# CortexM0_development_board.net
KiCad netlist of a schematic drawn in EAGLE
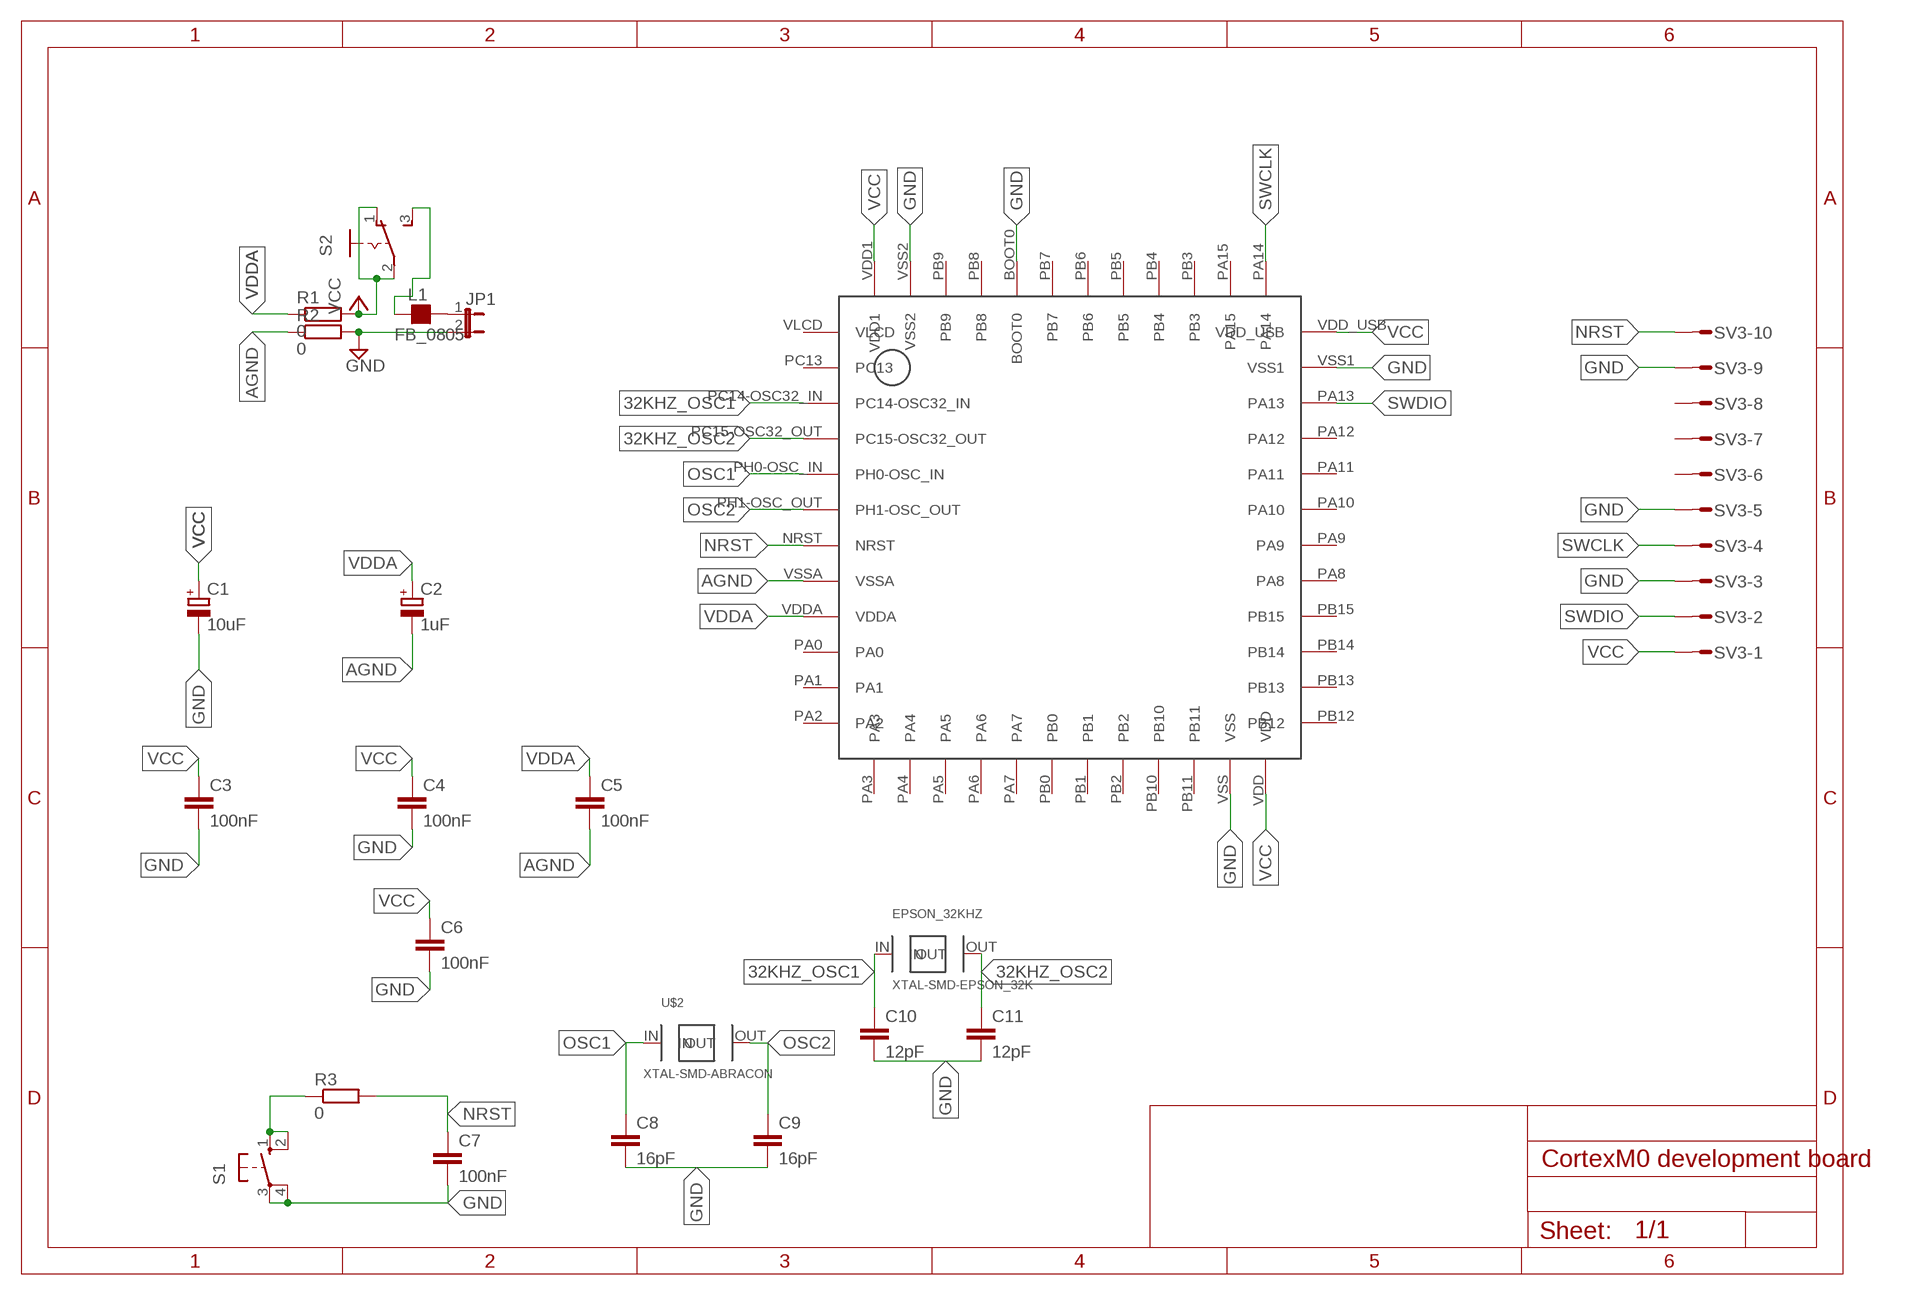
[diagram p0: schematic, sheet 1]

(export (version "E")
  (design (tool "Eeschema 10.0.6"))
  (components
    (comp (ref "C1")
      (value "10uF")
      (footprint "eagle-import:PANASONIC_B")
      (libsource (lib "eagle-import") (part "CPOL-EUB"))
    )
    (comp (ref "C2")
      (value "1uF")
      (footprint "eagle-import:PANASONIC_B")
      (libsource (lib "eagle-import") (part "CPOL-EUB"))
    )
    (comp (ref "C3")
      (value "100nF")
      (footprint "eagle-import:C0805")
      (libsource (lib "eagle-import") (part "C-EUC0805"))
    )
    (comp (ref "C4")
      (value "100nF")
      (footprint "eagle-import:C0805")
      (libsource (lib "eagle-import") (part "C-EUC0805"))
    )
    (comp (ref "C5")
      (value "100nF")
      (footprint "eagle-import:C0805")
      (libsource (lib "eagle-import") (part "C-EUC0805"))
    )
    (comp (ref "C6")
      (value "100nF")
      (footprint "eagle-import:C0805")
      (libsource (lib "eagle-import") (part "C-EUC0805"))
    )
    (comp (ref "C7")
      (value "100nF")
      (footprint "eagle-import:C0805")
      (libsource (lib "eagle-import") (part "C-EUC0805"))
    )
    (comp (ref "C8")
      (value "16pF")
      (footprint "eagle-import:C0805")
      (libsource (lib "eagle-import") (part "C-EUC0805"))
    )
    (comp (ref "C9")
      (value "16pF")
      (footprint "eagle-import:C0805")
      (libsource (lib "eagle-import") (part "C-EUC0805"))
    )
    (comp (ref "C10")
      (value "12pF")
      (footprint "eagle-import:C0805")
      (libsource (lib "eagle-import") (part "C-EUC0805"))
    )
    (comp (ref "C11")
      (value "12pF")
      (footprint "eagle-import:C0805")
      (libsource (lib "eagle-import") (part "C-EUC0805"))
    )
    (comp (ref "EPSON_32KHZ")
      (value "XTAL-SMD-EPSON_32K")
      (footprint "eagle-import:XTAL-EPSON-FC135R")
      (libsource (lib "eagle-import") (part "XTAL-SMD-EPSON_32K"))
    )
    (comp (ref "JP1")
      (value "JP1E")
      (footprint "eagle-import:JP1")
      (libsource (lib "eagle-import") (part "JP1E"))
    )
    (comp (ref "L1")
      (value "FB_0805")
      (footprint "eagle-import:L0805")
      (libsource (lib "eagle-import") (part "FB_0805"))
    )
    (comp (ref "R1")
      (value "0")
      (footprint "eagle-import:R0805")
      (libsource (lib "eagle-import") (part "R-EU_R0805"))
    )
    (comp (ref "R2")
      (value "0")
      (footprint "eagle-import:R0805")
      (libsource (lib "eagle-import") (part "R-EU_R0805"))
    )
    (comp (ref "R3")
      (value "0")
      (footprint "eagle-import:R0805")
      (libsource (lib "eagle-import") (part "R-EU_R0805"))
    )
    (comp (ref "S1")
      (value "10-XX")
      (footprint "eagle-import:B3F-10XX")
      (fields (field (name "MPN") "B3F-1000"))
      (libsource (lib "eagle-import") (part "10-XX"))
    )
    (comp (ref "S2")
      (value "255SB")
      (footprint "eagle-import:255SB")
      (libsource (lib "eagle-import") (part "255SB"))
    )
    (comp (ref "SV3")
      (value "S10P")
      (footprint "eagle-import:S10P")
      (libsource (lib "eagle-import") (part "S10P"))
    )
    (comp (ref "U$1")
      (value "STM32L083-LQFP48")
      (footprint "eagle-import:LQFP_48")
      (libsource (lib "eagle-import") (part "STM32L083-LQFP48"))
    )
    (comp (ref "U$2")
      (value "XTAL-SMD-ABRACON")
      (footprint "eagle-import:XTAL-SMD-ABRACON")
      (libsource (lib "eagle-import") (part "XTAL-SMD-ABRACON"))
    )
  )
  (nets
    (net (code "1") (name "32KHZ_OSC1") (class "Default")
      (node (ref "C10") (pin "1") (pinfunction "1_1") (pintype "passive"))
      (node (ref "EPSON_32KHZ") (pin "IN") (pinfunction "IN_IN") (pintype "bidirectional"))
      (node (ref "U$1") (pin "PC14-OSC32_IN") (pinfunction "PC14-OSC32_IN_PC14-OSC32_IN") (pintype "bidirectional"))
    )
    (net (code "2") (name "32KHZ_OSC2") (class "Default")
      (node (ref "C11") (pin "1") (pinfunction "1_1") (pintype "passive"))
      (node (ref "EPSON_32KHZ") (pin "OUT") (pinfunction "OUT_OUT") (pintype "bidirectional"))
      (node (ref "U$1") (pin "PC15-OSC32_OUT") (pinfunction "PC15-OSC32_OUT_PC15-OSC32_OUT") (pintype "bidirectional"))
    )
    (net (code "3") (name "AGND") (class "Default")
      (node (ref "C2") (pin "-") (pinfunction "-_-") (pintype "passive"))
      (node (ref "C5") (pin "2") (pinfunction "2_2") (pintype "passive"))
      (node (ref "R2") (pin "1") (pinfunction "1_1") (pintype "passive"))
      (node (ref "U$1") (pin "VSSA") (pinfunction "VSSA_VSSA") (pintype "bidirectional"))
    )
    (net (code "4") (name "GND") (class "Default")
      (node (ref "C1") (pin "-") (pinfunction "-_-") (pintype "passive"))
      (node (ref "C10") (pin "2") (pinfunction "2_2") (pintype "passive"))
      (node (ref "C11") (pin "2") (pinfunction "2_2") (pintype "passive"))
      (node (ref "C3") (pin "2") (pinfunction "2_2") (pintype "passive"))
      (node (ref "C4") (pin "2") (pinfunction "2_2") (pintype "passive"))
      (node (ref "C6") (pin "2") (pinfunction "2_2") (pintype "passive"))
      (node (ref "C7") (pin "2") (pinfunction "2_2") (pintype "passive"))
      (node (ref "C8") (pin "2") (pinfunction "2_2") (pintype "passive"))
      (node (ref "C9") (pin "2") (pinfunction "2_2") (pintype "passive"))
      (node (ref "JP1") (pin "2") (pinfunction "2_2") (pintype "passive"))
      (node (ref "R2") (pin "2") (pinfunction "2_2") (pintype "passive"))
      (node (ref "S1") (pin "3") (pinfunction "P_3") (pintype "passive"))
      (node (ref "S1") (pin "4") (pinfunction "P1_4") (pintype "passive"))
      (node (ref "SV3") (pin "3") (pinfunction "S_3") (pintype "passive"))
      (node (ref "SV3") (pin "5") (pinfunction "S_5") (pintype "passive"))
      (node (ref "SV3") (pin "9") (pinfunction "S_9") (pintype "passive"))
      (node (ref "U$1") (pin "BOOT0") (pinfunction "BOOT0_BOOT0") (pintype "bidirectional"))
      (node (ref "U$1") (pin "VSS") (pinfunction "VSS_VSS") (pintype "bidirectional"))
      (node (ref "U$1") (pin "VSS1") (pinfunction "VSS1_VSS1") (pintype "bidirectional"))
      (node (ref "U$1") (pin "VSS2") (pinfunction "VSS2_VSS2") (pintype "bidirectional"))
    )
    (net (code "5") (name "NRST") (class "Default")
      (node (ref "C7") (pin "1") (pinfunction "1_1") (pintype "passive"))
      (node (ref "R3") (pin "2") (pinfunction "2_2") (pintype "passive"))
      (node (ref "SV3") (pin "10") (pinfunction "S_10") (pintype "passive"))
      (node (ref "U$1") (pin "NRST") (pinfunction "NRST_NRST") (pintype "bidirectional"))
    )
    (net (code "6") (name "Net-(JP1-Pad1)") (class "Default")
      (node (ref "JP1") (pin "1") (pinfunction "1_1") (pintype "passive"))
      (node (ref "L1") (pin "2") (pinfunction "2_2") (pintype "passive"))
    )
    (net (code "7") (name "Net-(S1-S)") (class "Default")
      (node (ref "R3") (pin "1") (pinfunction "1_1") (pintype "passive"))
      (node (ref "S1") (pin "1") (pinfunction "S_1") (pintype "passive"))
      (node (ref "S1") (pin "2") (pinfunction "S1_2") (pintype "passive"))
    )
    (net (code "8") (name "Net-(S2-S)") (class "Default")
      (node (ref "L1") (pin "1") (pinfunction "1_1") (pintype "passive"))
      (node (ref "S2") (pin "3") (pinfunction "S_3") (pintype "passive"))
    )
    (net (code "9") (name "OSC1") (class "Default")
      (node (ref "C8") (pin "1") (pinfunction "1_1") (pintype "passive"))
      (node (ref "U$1") (pin "PH0-OSC_IN") (pinfunction "PH0-OSC_IN_PH0-OSC_IN") (pintype "bidirectional"))
      (node (ref "U$2") (pin "IN") (pinfunction "IN_IN") (pintype "bidirectional"))
    )
    (net (code "10") (name "OSC2") (class "Default")
      (node (ref "C9") (pin "1") (pinfunction "1_1") (pintype "passive"))
      (node (ref "U$1") (pin "PH1-OSC_OUT") (pinfunction "PH1-OSC_OUT_PH1-OSC_OUT") (pintype "bidirectional"))
      (node (ref "U$2") (pin "OUT") (pinfunction "OUT_OUT") (pintype "bidirectional"))
    )
    (net (code "11") (name "SWCLK") (class "Default")
      (node (ref "SV3") (pin "4") (pinfunction "S_4") (pintype "passive"))
      (node (ref "U$1") (pin "PA14") (pinfunction "PA14_PA14") (pintype "bidirectional"))
    )
    (net (code "12") (name "SWDIO") (class "Default")
      (node (ref "SV3") (pin "2") (pinfunction "S_2") (pintype "passive"))
      (node (ref "U$1") (pin "PA13") (pinfunction "PA13_PA13") (pintype "bidirectional"))
    )
    (net (code "13") (name "VCC") (class "Default")
      (node (ref "C1") (pin "+") (pinfunction "+_+") (pintype "passive"))
      (node (ref "C3") (pin "1") (pinfunction "1_1") (pintype "passive"))
      (node (ref "C4") (pin "1") (pinfunction "1_1") (pintype "passive"))
      (node (ref "C6") (pin "1") (pinfunction "1_1") (pintype "passive"))
      (node (ref "R1") (pin "2") (pinfunction "2_2") (pintype "passive"))
      (node (ref "S2") (pin "1") (pinfunction "O_1") (pintype "passive"))
      (node (ref "S2") (pin "2") (pinfunction "P_2") (pintype "passive"))
      (node (ref "SV3") (pin "1") (pinfunction "S_1") (pintype "passive"))
      (node (ref "U$1") (pin "VDD") (pinfunction "VDD_VDD") (pintype "bidirectional"))
      (node (ref "U$1") (pin "VDD1") (pinfunction "VDD1_VDD1") (pintype "bidirectional"))
      (node (ref "U$1") (pin "VDD_USB") (pinfunction "VDD_USB_VDD_USB") (pintype "bidirectional"))
    )
    (net (code "14") (name "VDDA") (class "Default")
      (node (ref "C2") (pin "+") (pinfunction "+_+") (pintype "passive"))
      (node (ref "C5") (pin "1") (pinfunction "1_1") (pintype "passive"))
      (node (ref "R1") (pin "1") (pinfunction "1_1") (pintype "passive"))
      (node (ref "U$1") (pin "VDDA") (pinfunction "VDDA_VDDA") (pintype "bidirectional"))
    )
    (net (code "15") (name "unconnected-(SV3G-S-Pad6)") (class "Default")
      (node (ref "SV3") (pin "6") (pinfunction "S_6") (pintype "passive"))
    )
    (net (code "16") (name "unconnected-(SV3H-S-Pad7)") (class "Default")
      (node (ref "SV3") (pin "7") (pinfunction "S_7") (pintype "passive"))
    )
    (net (code "17") (name "unconnected-(SV3I-S-Pad8)") (class "Default")
      (node (ref "SV3") (pin "8") (pinfunction "S_8") (pintype "passive"))
    )
    (net (code "18") (name "unconnected-(U$1-PadPA0)") (class "Default")
      (node (ref "U$1") (pin "PA0") (pinfunction "PA0_PA0") (pintype "bidirectional"))
    )
    (net (code "19") (name "unconnected-(U$1-PadPA1)") (class "Default")
      (node (ref "U$1") (pin "PA1") (pinfunction "PA1_PA1") (pintype "bidirectional"))
    )
    (net (code "20") (name "unconnected-(U$1-PadPA2)") (class "Default")
      (node (ref "U$1") (pin "PA2") (pinfunction "PA2_PA2") (pintype "bidirectional"))
    )
    (net (code "21") (name "unconnected-(U$1-PadPA3)") (class "Default")
      (node (ref "U$1") (pin "PA3") (pinfunction "PA3_PA3") (pintype "bidirectional"))
    )
    (net (code "22") (name "unconnected-(U$1-PadPA4)") (class "Default")
      (node (ref "U$1") (pin "PA4") (pinfunction "PA4_PA4") (pintype "bidirectional"))
    )
    (net (code "23") (name "unconnected-(U$1-PadPA5)") (class "Default")
      (node (ref "U$1") (pin "PA5") (pinfunction "PA5_PA5") (pintype "bidirectional"))
    )
    (net (code "24") (name "unconnected-(U$1-PadPA6)") (class "Default")
      (node (ref "U$1") (pin "PA6") (pinfunction "PA6_PA6") (pintype "bidirectional"))
    )
    (net (code "25") (name "unconnected-(U$1-PadPA7)") (class "Default")
      (node (ref "U$1") (pin "PA7") (pinfunction "PA7_PA7") (pintype "bidirectional"))
    )
    (net (code "26") (name "unconnected-(U$1-PadPA8)") (class "Default")
      (node (ref "U$1") (pin "PA8") (pinfunction "PA8_PA8") (pintype "bidirectional"))
    )
    (net (code "27") (name "unconnected-(U$1-PadPA9)") (class "Default")
      (node (ref "U$1") (pin "PA9") (pinfunction "PA9_PA9") (pintype "bidirectional"))
    )
    (net (code "28") (name "unconnected-(U$1-PadPA10)") (class "Default")
      (node (ref "U$1") (pin "PA10") (pinfunction "PA10_PA10") (pintype "bidirectional"))
    )
    (net (code "29") (name "unconnected-(U$1-PadPA11)") (class "Default")
      (node (ref "U$1") (pin "PA11") (pinfunction "PA11_PA11") (pintype "bidirectional"))
    )
    (net (code "30") (name "unconnected-(U$1-PadPA12)") (class "Default")
      (node (ref "U$1") (pin "PA12") (pinfunction "PA12_PA12") (pintype "bidirectional"))
    )
    (net (code "31") (name "unconnected-(U$1-PadPA15)") (class "Default")
      (node (ref "U$1") (pin "PA15") (pinfunction "PA15_PA15") (pintype "bidirectional"))
    )
    (net (code "32") (name "unconnected-(U$1-PadPB0)") (class "Default")
      (node (ref "U$1") (pin "PB0") (pinfunction "PB0_PB0") (pintype "bidirectional"))
    )
    (net (code "33") (name "unconnected-(U$1-PadPB1)") (class "Default")
      (node (ref "U$1") (pin "PB1") (pinfunction "PB1_PB1") (pintype "bidirectional"))
    )
    (net (code "34") (name "unconnected-(U$1-PadPB2)") (class "Default")
      (node (ref "U$1") (pin "PB2") (pinfunction "PB2_PB2") (pintype "bidirectional"))
    )
    (net (code "35") (name "unconnected-(U$1-PadPB3)") (class "Default")
      (node (ref "U$1") (pin "PB3") (pinfunction "PB3_PB3") (pintype "bidirectional"))
    )
    (net (code "36") (name "unconnected-(U$1-PadPB4)") (class "Default")
      (node (ref "U$1") (pin "PB4") (pinfunction "PB4_PB4") (pintype "bidirectional"))
    )
    (net (code "37") (name "unconnected-(U$1-PadPB5)") (class "Default")
      (node (ref "U$1") (pin "PB5") (pinfunction "PB5_PB5") (pintype "bidirectional"))
    )
    (net (code "38") (name "unconnected-(U$1-PadPB6)") (class "Default")
      (node (ref "U$1") (pin "PB6") (pinfunction "PB6_PB6") (pintype "bidirectional"))
    )
    (net (code "39") (name "unconnected-(U$1-PadPB7)") (class "Default")
      (node (ref "U$1") (pin "PB7") (pinfunction "PB7_PB7") (pintype "bidirectional"))
    )
    (net (code "40") (name "unconnected-(U$1-PadPB8)") (class "Default")
      (node (ref "U$1") (pin "PB8") (pinfunction "PB8_PB8") (pintype "bidirectional"))
    )
    (net (code "41") (name "unconnected-(U$1-PadPB9)") (class "Default")
      (node (ref "U$1") (pin "PB9") (pinfunction "PB9_PB9") (pintype "bidirectional"))
    )
    (net (code "42") (name "unconnected-(U$1-PadPB10)") (class "Default")
      (node (ref "U$1") (pin "PB10") (pinfunction "PB10_PB10") (pintype "bidirectional"))
    )
    (net (code "43") (name "unconnected-(U$1-PadPB11)") (class "Default")
      (node (ref "U$1") (pin "PB11") (pinfunction "PB11_PB11") (pintype "bidirectional"))
    )
    (net (code "44") (name "unconnected-(U$1-PadPB12)") (class "Default")
      (node (ref "U$1") (pin "PB12") (pinfunction "PB12_PB12") (pintype "bidirectional"))
    )
    (net (code "45") (name "unconnected-(U$1-PadPB13)") (class "Default")
      (node (ref "U$1") (pin "PB13") (pinfunction "PB13_PB13") (pintype "bidirectional"))
    )
    (net (code "46") (name "unconnected-(U$1-PadPB14)") (class "Default")
      (node (ref "U$1") (pin "PB14") (pinfunction "PB14_PB14") (pintype "bidirectional"))
    )
    (net (code "47") (name "unconnected-(U$1-PadPB15)") (class "Default")
      (node (ref "U$1") (pin "PB15") (pinfunction "PB15_PB15") (pintype "bidirectional"))
    )
    (net (code "48") (name "unconnected-(U$1-PadPC13)") (class "Default")
      (node (ref "U$1") (pin "PC13") (pinfunction "PC13_PC13") (pintype "bidirectional"))
    )
    (net (code "49") (name "unconnected-(U$1-PadVLCD)") (class "Default")
      (node (ref "U$1") (pin "VLCD") (pinfunction "VLCD_VLCD") (pintype "bidirectional"))
    )
  )
)
